# Sheet2.net
KiCad netlist of a schematic drawn in Altium Designer
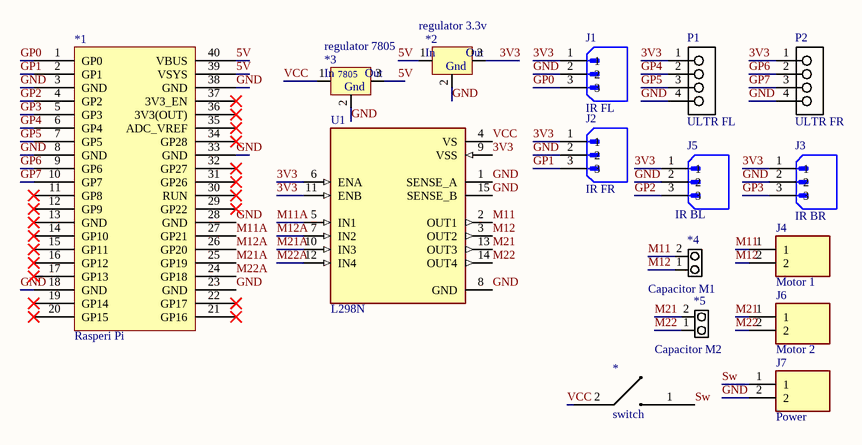
[diagram p0: Sheet2.SchDoc]

(export (version "E")
  (design (tool "Eeschema 10.0.6"))
  (components
    (comp (ref "*") (value "switch") (footprint "switch") (libsource (lib "Schlib1") (part "switch")))
    (comp (ref "*1")
      (value "Rasperi Pi")
      (footprint "Rasperi Pi")
      (libsource (lib "Schlib1") (part "Rasperi Pi"))
    )
    (comp (ref "*2")
      (value "regulator 3.3v")
      (footprint "Regulator 3.3V")
      (libsource (lib "Schlib1") (part "regulator 3.3v"))
    )
    (comp (ref "*3")
      (value "regulator 7805")
      (footprint "Regulator 7805")
      (libsource (lib "Schlib1") (part "regulator 7805"))
    )
    (comp (ref "*4")
      (value "Capacitor M1")
      (footprint "Capacitor")
      (libsource (lib "Schlib1") (part "Capacitor"))
    )
    (comp (ref "*5")
      (value "Capacitor M2")
      (footprint "Capacitor")
      (libsource (lib "Schlib1") (part "Capacitor"))
    )
    (comp (ref "J1")
      (value "IR FL")
      (footprint "3pin jst")
      (description "Connector Header Through Hole 3 position 0.098 (2.50mm)")
      (fields (field (name "MP") "B3B-XH-A(LF)(SN)") (field (name "MF") "JST Sales"))
      (libsource (lib "Schlib1") (part "3pin jst"))
    )
    (comp (ref "J2")
      (value "IR FR")
      (footprint "3pin jst")
      (description "Connector Header Through Hole 3 position 0.098 (2.50mm)")
      (fields (field (name "MP") "B3B-XH-A(LF)(SN)") (field (name "MF") "JST Sales"))
      (libsource (lib "Schlib1") (part "3pin jst"))
    )
    (comp (ref "J3")
      (value "IR BR")
      (footprint "3pin jst")
      (description "Connector Header Through Hole 3 position 0.098 (2.50mm)")
      (fields (field (name "MP") "B3B-XH-A(LF)(SN)") (field (name "MF") "JST Sales"))
      (libsource (lib "Schlib1") (part "3pin jst"))
    )
    (comp (ref "J4")
      (value "Motor 1")
      (footprint "Power Terminal block")
      (description "Conn Terminal Block 2 POS 9.53mm Solder ST Thru-Hole 25A/Contact")
      (fields (field (name "MF") "TE Connectivity / AMP") (field (name "MP") "4-1437652-6"))
      (libsource (lib "Schlib1") (part "Power Terminal block"))
    )
    (comp (ref "J5")
      (value "IR BL")
      (footprint "3pin jst")
      (description "Connector Header Through Hole 3 position 0.098 (2.50mm)")
      (fields (field (name "MP") "B3B-XH-A(LF)(SN)") (field (name "MF") "JST Sales"))
      (libsource (lib "Schlib1") (part "3pin jst"))
    )
    (comp (ref "J6")
      (value "Motor 2")
      (footprint "Power Terminal block")
      (description "Conn Terminal Block 2 POS 9.53mm Solder ST Thru-Hole 25A/Contact")
      (fields (field (name "MF") "TE Connectivity / AMP") (field (name "MP") "4-1437652-6"))
      (libsource (lib "Schlib1") (part "Power Terminal block"))
    )
    (comp (ref "J7")
      (value "Power")
      (footprint "Power Terminal block")
      (description "Conn Terminal Block 2 POS 9.53mm Solder ST Thru-Hole 25A/Contact")
      (fields (field (name "MF") "TE Connectivity / AMP") (field (name "MP") "4-1437652-6"))
      (libsource (lib "Schlib1") (part "Power Terminal block"))
    )
    (comp (ref "P1")
      (value "ULTR FL")
      (footprint "4pin jst")
      (description "Connector Header Through Hole 4 position 0.079 (2.00mm)")
      (fields (field (name "MP") "B4B-PH-K") (field (name "MF") "JST"))
      (libsource (lib "Schlib1") (part "4pin jst"))
    )
    (comp (ref "P2")
      (value "ULTR FR")
      (footprint "4pin jst")
      (description "Connector Header Through Hole 4 position 0.079 (2.00mm)")
      (fields (field (name "MP") "B4B-PH-K") (field (name "MF") "JST"))
      (libsource (lib "Schlib1") (part "4pin jst"))
    )
    (comp (ref "U1")
      (value "L298N")
      (footprint "L298N")
      (description "Dual Full Bridge Motor Driver 15-Pin(15+Tab) MULTIWATT V Tube")
      (libsource (lib "Schlib1") (part "L298N"))
    )
  )
  (nets
    (net (code "1") (name "/3V3") (class "Default")
      (node (ref "*2") (pin "3") (pinfunction "Output_3") (pintype "passive"))
      (node (ref "J1") (pin "1") (pinfunction "1_1") (pintype "passive"))
      (node (ref "J2") (pin "1") (pinfunction "1_1") (pintype "passive"))
      (node (ref "J3") (pin "1") (pinfunction "1_1") (pintype "passive"))
      (node (ref "J5") (pin "1") (pinfunction "1_1") (pintype "passive"))
      (node (ref "P1") (pin "1") (pinfunction "1_1") (pintype "passive"))
      (node (ref "P2") (pin "1") (pinfunction "1_1") (pintype "passive"))
      (node (ref "U1") (pin "11") (pinfunction "ENB_11") (pintype "input"))
      (node (ref "U1") (pin "6") (pinfunction "ENA_6") (pintype "input"))
      (node (ref "U1") (pin "9") (pinfunction "VSS_9") (pintype "input"))
    )
    (net (code "2") (name "/5V") (class "Default")
      (node (ref "*1") (pin "39") (pinfunction "VSYS_39") (pintype "passive"))
      (node (ref "*1") (pin "40") (pinfunction "VBUS_40") (pintype "passive"))
      (node (ref "*2") (pin "1") (pinfunction "input_1") (pintype "passive"))
      (node (ref "*3") (pin "3") (pinfunction "Output_3") (pintype "passive"))
    )
    (net (code "3") (name "/GND") (class "Default")
      (node (ref "*1") (pin "18") (pinfunction "GND_18") (pintype "passive"))
      (node (ref "*1") (pin "23") (pinfunction "GND_23") (pintype "passive"))
      (node (ref "*1") (pin "28") (pinfunction "GND_28") (pintype "passive"))
      (node (ref "*1") (pin "3") (pinfunction "GND_3") (pintype "passive"))
      (node (ref "*1") (pin "33") (pinfunction "GND_33") (pintype "passive"))
      (node (ref "*1") (pin "38") (pinfunction "GND_38") (pintype "passive"))
      (node (ref "*1") (pin "8") (pinfunction "GND_8") (pintype "passive"))
      (node (ref "*2") (pin "2") (pinfunction "Ground_2") (pintype "passive"))
      (node (ref "*3") (pin "2") (pinfunction "Ground_2") (pintype "passive"))
      (node (ref "J1") (pin "2") (pinfunction "2_2") (pintype "passive"))
      (node (ref "J2") (pin "2") (pinfunction "2_2") (pintype "passive"))
      (node (ref "J3") (pin "2") (pinfunction "2_2") (pintype "passive"))
      (node (ref "J5") (pin "2") (pinfunction "2_2") (pintype "passive"))
      (node (ref "J7") (pin "2") (pinfunction "2_2") (pintype "passive"))
      (node (ref "P1") (pin "4") (pinfunction "4_4") (pintype "passive"))
      (node (ref "P2") (pin "4") (pinfunction "4_4") (pintype "passive"))
      (node (ref "U1") (pin "1") (pinfunction "SENSE_A_1") (pintype "passive"))
      (node (ref "U1") (pin "15") (pinfunction "SENSE_B_15") (pintype "passive"))
      (node (ref "U1") (pin "8") (pinfunction "GND_8") (pintype "power_in"))
    )
    (net (code "4") (name "/GP0") (class "Default")
      (node (ref "*1") (pin "1") (pinfunction "GP0_1") (pintype "passive"))
      (node (ref "J1") (pin "3") (pinfunction "3_3") (pintype "passive"))
    )
    (net (code "5") (name "/GP1") (class "Default")
      (node (ref "*1") (pin "2") (pinfunction "GP1_2") (pintype "passive"))
      (node (ref "J2") (pin "3") (pinfunction "3_3") (pintype "passive"))
    )
    (net (code "6") (name "/GP2") (class "Default")
      (node (ref "*1") (pin "4") (pinfunction "GP2_4") (pintype "passive"))
      (node (ref "J5") (pin "3") (pinfunction "3_3") (pintype "passive"))
    )
    (net (code "7") (name "/GP3") (class "Default")
      (node (ref "*1") (pin "5") (pinfunction "GP3_5") (pintype "passive"))
      (node (ref "J3") (pin "3") (pinfunction "3_3") (pintype "passive"))
    )
    (net (code "8") (name "/GP4") (class "Default")
      (node (ref "*1") (pin "6") (pinfunction "GP4_6") (pintype "passive"))
      (node (ref "P1") (pin "2") (pinfunction "2_2") (pintype "passive"))
    )
    (net (code "9") (name "/GP5") (class "Default")
      (node (ref "*1") (pin "7") (pinfunction "GP5_7") (pintype "passive"))
      (node (ref "P1") (pin "3") (pinfunction "3_3") (pintype "passive"))
    )
    (net (code "10") (name "/GP6") (class "Default")
      (node (ref "*1") (pin "9") (pinfunction "GP6_9") (pintype "passive"))
      (node (ref "P2") (pin "2") (pinfunction "2_2") (pintype "passive"))
    )
    (net (code "11") (name "/GP7") (class "Default")
      (node (ref "*1") (pin "10") (pinfunction "GP7_10") (pintype "passive"))
      (node (ref "P2") (pin "3") (pinfunction "3_3") (pintype "passive"))
    )
    (net (code "12") (name "/M11") (class "Default")
      (node (ref "*4") (pin "2") (pinfunction "2_2") (pintype "passive"))
      (node (ref "J4") (pin "1") (pinfunction "1_1") (pintype "passive"))
      (node (ref "U1") (pin "2") (pinfunction "OUT1_2") (pintype "output"))
    )
    (net (code "13") (name "/M11A") (class "Default")
      (node (ref "*1") (pin "27") (pinfunction "GP21_27") (pintype "passive"))
      (node (ref "U1") (pin "5") (pinfunction "IN1_5") (pintype "input"))
    )
    (net (code "14") (name "/M12") (class "Default")
      (node (ref "*4") (pin "1") (pinfunction "1_1") (pintype "passive"))
      (node (ref "J4") (pin "2") (pinfunction "2_2") (pintype "passive"))
      (node (ref "U1") (pin "3") (pinfunction "OUT2_3") (pintype "output"))
    )
    (net (code "15") (name "/M12A") (class "Default")
      (node (ref "*1") (pin "26") (pinfunction "GP20_26") (pintype "passive"))
      (node (ref "U1") (pin "7") (pinfunction "IN2_7") (pintype "input"))
    )
    (net (code "16") (name "/M21") (class "Default")
      (node (ref "*5") (pin "2") (pinfunction "2_2") (pintype "passive"))
      (node (ref "J6") (pin "1") (pinfunction "1_1") (pintype "passive"))
      (node (ref "U1") (pin "13") (pinfunction "OUT3_13") (pintype "output"))
    )
    (net (code "17") (name "/M21A") (class "Default")
      (node (ref "*1") (pin "25") (pinfunction "GP19_25") (pintype "passive"))
      (node (ref "U1") (pin "10") (pinfunction "IN3_10") (pintype "input"))
    )
    (net (code "18") (name "/M22") (class "Default")
      (node (ref "*5") (pin "1") (pinfunction "1_1") (pintype "passive"))
      (node (ref "J6") (pin "2") (pinfunction "2_2") (pintype "passive"))
      (node (ref "U1") (pin "14") (pinfunction "OUT4_14") (pintype "output"))
    )
    (net (code "19") (name "/M22A") (class "Default")
      (node (ref "*1") (pin "24") (pinfunction "GP18_24") (pintype "passive"))
      (node (ref "U1") (pin "12") (pinfunction "IN4_12") (pintype "input"))
    )
    (net (code "20") (name "/Sw") (class "Default")
      (node (ref "*") (pin "1") (pinfunction "1_1") (pintype "passive"))
      (node (ref "J7") (pin "1") (pinfunction "1_1") (pintype "passive"))
    )
    (net (code "21") (name "/VCC") (class "Default")
      (node (ref "*") (pin "2") (pinfunction "2_2") (pintype "passive"))
      (node (ref "*3") (pin "1") (pinfunction "input_1") (pintype "passive"))
      (node (ref "U1") (pin "4") (pinfunction "VS_4") (pintype "power_in"))
    )
    (net (code "22") (name "unconnected-(*1-3V3(OUT)-Pad36)") (class "Default")
      (node (ref "*1") (pin "36") (pinfunction "3V3(OUT)_36") (pintype "passive+no_connect"))
    )
    (net (code "23") (name "unconnected-(*1-3V3_EN-Pad37)") (class "Default")
      (node (ref "*1") (pin "37") (pinfunction "3V3_EN_37") (pintype "passive+no_connect"))
    )
    (net (code "24") (name "unconnected-(*1-ADC_VREF-Pad35)") (class "Default")
      (node (ref "*1") (pin "35") (pinfunction "ADC_VREF_35") (pintype "passive+no_connect"))
    )
    (net (code "25") (name "unconnected-(*1-GND-Pad13)") (class "Default")
      (node (ref "*1") (pin "13") (pinfunction "GND_13") (pintype "passive+no_connect"))
    )
    (net (code "26") (name "unconnected-(*1-GP8-Pad11)") (class "Default")
      (node (ref "*1") (pin "11") (pinfunction "GP8_11") (pintype "passive+no_connect"))
    )
    (net (code "27") (name "unconnected-(*1-GP9-Pad12)") (class "Default")
      (node (ref "*1") (pin "12") (pinfunction "GP9_12") (pintype "passive+no_connect"))
    )
    (net (code "28") (name "unconnected-(*1-GP10-Pad14)") (class "Default")
      (node (ref "*1") (pin "14") (pinfunction "GP10_14") (pintype "passive+no_connect"))
    )
    (net (code "29") (name "unconnected-(*1-GP11-Pad15)") (class "Default")
      (node (ref "*1") (pin "15") (pinfunction "GP11_15") (pintype "passive+no_connect"))
    )
    (net (code "30") (name "unconnected-(*1-GP12-Pad16)") (class "Default")
      (node (ref "*1") (pin "16") (pinfunction "GP12_16") (pintype "passive+no_connect"))
    )
    (net (code "31") (name "unconnected-(*1-GP13-Pad17)") (class "Default")
      (node (ref "*1") (pin "17") (pinfunction "GP13_17") (pintype "passive+no_connect"))
    )
    (net (code "32") (name "unconnected-(*1-GP14-Pad19)") (class "Default")
      (node (ref "*1") (pin "19") (pinfunction "GP14_19") (pintype "passive+no_connect"))
    )
    (net (code "33") (name "unconnected-(*1-GP15-Pad20)") (class "Default")
      (node (ref "*1") (pin "20") (pinfunction "GP15_20") (pintype "passive+no_connect"))
    )
    (net (code "34") (name "unconnected-(*1-GP16-Pad21)") (class "Default")
      (node (ref "*1") (pin "21") (pinfunction "GP16_21") (pintype "passive+no_connect"))
    )
    (net (code "35") (name "unconnected-(*1-GP17-Pad22)") (class "Default")
      (node (ref "*1") (pin "22") (pinfunction "GP17_22") (pintype "passive+no_connect"))
    )
    (net (code "36") (name "unconnected-(*1-GP22-Pad29)") (class "Default")
      (node (ref "*1") (pin "29") (pinfunction "GP22_29") (pintype "passive+no_connect"))
    )
    (net (code "37") (name "unconnected-(*1-GP26-Pad31)") (class "Default")
      (node (ref "*1") (pin "31") (pinfunction "GP26_31") (pintype "passive+no_connect"))
    )
    (net (code "38") (name "unconnected-(*1-GP27-Pad32)") (class "Default")
      (node (ref "*1") (pin "32") (pinfunction "GP27_32") (pintype "passive+no_connect"))
    )
    (net (code "39") (name "unconnected-(*1-GP28-Pad34)") (class "Default")
      (node (ref "*1") (pin "34") (pinfunction "GP28_34") (pintype "passive+no_connect"))
    )
    (net (code "40") (name "unconnected-(*1-RUN-Pad30)") (class "Default")
      (node (ref "*1") (pin "30") (pinfunction "RUN_30") (pintype "passive+no_connect"))
    )
  )
)
